# 531_RS26.net
KiCad netlist of a schematic drawn in Altium Designer
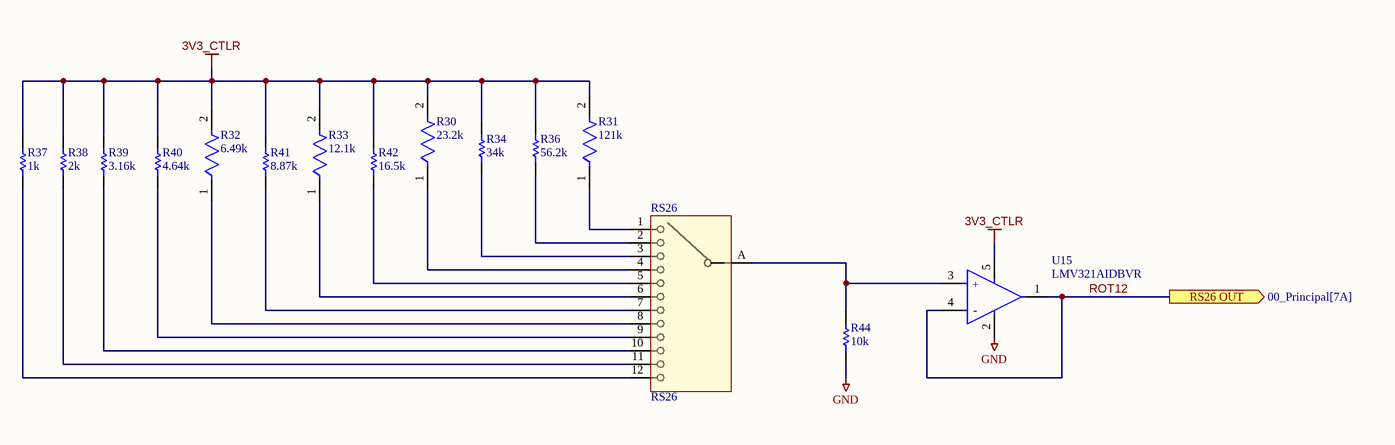
[diagram p0: 531_RS26.SchDoc]

(export (version "E")
  (design (tool "Eeschema 10.0.6"))
  (components
    (comp (ref "R30")
      (value "23.2k")
      (footprint "FP-ERJ2R-MFG")
      (description "RES SMD 23.2K OHM 1% 1/10W 0402")
      (fields
        (field (name "MANUFACTURER PART NUMBER") "ERJ-2RKF2322X")
        (field (name "MANUFACTURER") "Panasonic")
      )
      (libsource (lib "Altium Content Vault") (part "1029c3af85768c4190bb7ad29bc67b5"))
    )
    (comp (ref "R31")
      (value "121k")
      (footprint "FP-ERJ2R-MFG")
      (description "RES SMD 121K OHM 1% 1/10W 0402")
      (fields
        (field (name "OCTOPART") "https://octopart.com/erj-2rkf1213x-panasonic-55420883")
        (field (name "MANUFACTURER") "Panasonic")
      )
      (libsource (lib "Altium Content Vault") (part "1029c3af85768c4190bb7ad29bc67b5"))
    )
    (comp (ref "R32")
      (value "6.49k")
      (footprint "FP-ERJ2RK-MFG")
      (fields (field (name "TOLERANCE") "1%"))
      (libsource (lib "Altium Content Vault") (part "1029c3af85768c4190bb7ad29bc67b5"))
    )
    (comp (ref "R33")
      (value "12.1k")
      (footprint "FP-ERJ2RK-IPC_C")
      (description "RES SMD 12.1K OHM 1% 1/10W 0402")
      (fields (field (name "TOLERANCE") "1%"))
      (libsource (lib "Altium Content Vault") (part "1029c3af85768c4190bb7ad29bc67b5"))
    )
    (comp (ref "R34")
      (value "34k")
      (footprint "RESC1005X40X25LL05T05")
      (fields (field (name "PART NUMBER") "ERJ-2RKF3402X") (field (name "MANUFACTURER") "Panasonic"))
      (libsource (lib "Altium Content Vault") (part "RES"))
    )
    (comp (ref "R36")
      (value "56.2k")
      (footprint "RESC1005X40X25LL05T05")
      (fields (field (name "PART NUMBER") "ERJ-2RKF5622X") (field (name "MANUFACTURER") "Panasonic"))
      (libsource (lib "Altium Content Vault") (part "RES"))
    )
    (comp (ref "R37")
      (value "1k")
      (footprint "RESC1005X40X25NL05T05")
      (description "Chip Resistor, 1 KOhm, +/- 1%, 100 mW, -55 to 155 degC, 0402 (1005 Metric), RoHS, Tape and Reel")
      (fields (field (name "PARTNUMBER") "ERJ-2RKF1001X") (field (name "MANUFACTURER") "Basic Passives"))
      (libsource (lib "Altium Content Vault") (part "RES-2"))
    )
    (comp (ref "R38")
      (value "2k")
      (footprint "RESC1005X40X25LL10T10")
      (fields (field (name "MANUFACTURER") "Panasonic") (field (name "PART NUMBER") "ERA-2AEB202X"))
      (libsource (lib "Altium Content Vault") (part "RES"))
    )
    (comp (ref "R39")
      (value "3.16k")
      (footprint "RESC1005X40X25ML05T05")
      (fields (field (name "MANUFACTURER") "Panasonic") (field (name "PART NUMBER") "ERJ-2RKF3161X"))
      (libsource (lib "Altium Content Vault") (part "RES"))
    )
    (comp (ref "R40")
      (value "4.64k")
      (footprint "RESC1005X40X25LL05T05")
      (fields (field (name "PART NUMBER") "ERJ-2RKF4641X") (field (name "MANUFACTURER") "Panasonic"))
      (libsource (lib "Altium Content Vault") (part "RES"))
    )
    (comp (ref "R41")
      (value "8.87k")
      (footprint "RESC1005X40X25NL05T05")
      (fields (field (name "PART NUMBER") "ERJ-2RKF8871X") (field (name "MANUFACTURER") "Panasonic"))
      (libsource (lib "Altium Content Vault") (part "RES"))
    )
    (comp (ref "R42")
      (value "16.5k")
      (footprint "RESC1005X40X25LL05T05")
      (fields (field (name "PART NUMBER") "ERJ-2RKF1652X") (field (name "MANUFACTURER") "Panasonic"))
      (libsource (lib "Altium Content Vault") (part "RES"))
    )
    (comp (ref "R44")
      (value "10k")
      (footprint "RESC1005X40X25ML05T05")
      (fields (field (name "MANUFACTURER") "Panasonic") (field (name "PART NUMBER") "ERJ-2RHD1002X"))
      (libsource (lib "Altium Content Vault") (part "RES"))
    )
    (comp (ref "RS26")
      (value "RS26")
      (footprint "RS26")
      (description "RS26 Rotary Type Band Switch Position Switch")
      (libsource (lib "Esquemas") (part "RS26 Rotary Coder"))
    )
    (comp (ref "U15")
      (value "LMV321AIDBVR")
      (footprint "FP-DBV0005A-MFG")
      (description "IC OPAMP GP 1 CIRCUIT SOT23-5")
      (libsource (lib "Altium Content Vault") (part "1dcd28e651784f0a5a8ed6f8452eeff"))
    )
  )
  (nets
    (net (code "1") (name "/ROT12") (class "Default")
      (node (ref "U15") (pin "1") (pinfunction "OUT_1") (pintype "passive"))
      (node (ref "U15") (pin "4") (pinfunction "-IN_4") (pintype "tri_state"))
    )
    (net (code "2") (name "3V3_CTLR") (class "Default")
      (node (ref "R30") (pin "2") (pinfunction "2_2") (pintype "passive"))
      (node (ref "R31") (pin "2") (pinfunction "2_2") (pintype "passive"))
      (node (ref "R32") (pin "2") (pinfunction "2_2") (pintype "passive"))
      (node (ref "R33") (pin "2") (pinfunction "2_2") (pintype "passive"))
      (node (ref "R34") (pin "2") (pinfunction "2_2") (pintype "passive"))
      (node (ref "R36") (pin "2") (pinfunction "2_2") (pintype "passive"))
      (node (ref "R37") (pin "2") (pinfunction "2_2") (pintype "passive"))
      (node (ref "R38") (pin "2") (pinfunction "2_2") (pintype "passive"))
      (node (ref "R39") (pin "2") (pinfunction "2_2") (pintype "passive"))
      (node (ref "R40") (pin "2") (pinfunction "2_2") (pintype "passive"))
      (node (ref "R41") (pin "2") (pinfunction "2_2") (pintype "passive"))
      (node (ref "R42") (pin "2") (pinfunction "2_2") (pintype "passive"))
      (node (ref "U15") (pin "5") (pinfunction "V+_5") (pintype "passive"))
    )
    (net (code "3") (name "GND") (class "Default")
      (node (ref "R44") (pin "1") (pinfunction "1_1") (pintype "passive"))
      (node (ref "U15") (pin "2") (pinfunction "V-_2") (pintype "passive"))
    )
    (net (code "4") (name "Net-(R30-Pad1)") (class "Default")
      (node (ref "R30") (pin "1") (pinfunction "1_1") (pintype "passive"))
      (node (ref "RS26") (pin "4") (pinfunction "A_4") (pintype "passive"))
    )
    (net (code "5") (name "Net-(R31-Pad1)") (class "Default")
      (node (ref "R31") (pin "1") (pinfunction "1_1") (pintype "passive"))
      (node (ref "RS26") (pin "1") (pinfunction "A_1") (pintype "passive"))
    )
    (net (code "6") (name "Net-(R32-Pad1)") (class "Default")
      (node (ref "R32") (pin "1") (pinfunction "1_1") (pintype "passive"))
      (node (ref "RS26") (pin "8") (pinfunction "A_8") (pintype "passive"))
    )
    (net (code "7") (name "Net-(R33-Pad1)") (class "Default")
      (node (ref "R33") (pin "1") (pinfunction "1_1") (pintype "passive"))
      (node (ref "RS26") (pin "6") (pinfunction "A_6") (pintype "passive"))
    )
    (net (code "8") (name "Net-(R34-Pad1)") (class "Default")
      (node (ref "R34") (pin "1") (pinfunction "1_1") (pintype "passive"))
      (node (ref "RS26") (pin "3") (pinfunction "A_3") (pintype "passive"))
    )
    (net (code "9") (name "Net-(R36-Pad1)") (class "Default")
      (node (ref "R36") (pin "1") (pinfunction "1_1") (pintype "passive"))
      (node (ref "RS26") (pin "2") (pinfunction "A_2") (pintype "passive"))
    )
    (net (code "10") (name "Net-(R37-Pad1)") (class "Default")
      (node (ref "R37") (pin "1") (pinfunction "1_1") (pintype "passive"))
      (node (ref "RS26") (pin "12") (pinfunction "A_12") (pintype "passive"))
    )
    (net (code "11") (name "Net-(R38-Pad1)") (class "Default")
      (node (ref "R38") (pin "1") (pinfunction "1_1") (pintype "passive"))
      (node (ref "RS26") (pin "11") (pinfunction "A_11") (pintype "passive"))
    )
    (net (code "12") (name "Net-(R39-Pad1)") (class "Default")
      (node (ref "R39") (pin "1") (pinfunction "1_1") (pintype "passive"))
      (node (ref "RS26") (pin "10") (pinfunction "A_10") (pintype "passive"))
    )
    (net (code "13") (name "Net-(R40-Pad1)") (class "Default")
      (node (ref "R40") (pin "1") (pinfunction "1_1") (pintype "passive"))
      (node (ref "RS26") (pin "9") (pinfunction "A_9") (pintype "passive"))
    )
    (net (code "14") (name "Net-(R41-Pad1)") (class "Default")
      (node (ref "R41") (pin "1") (pinfunction "1_1") (pintype "passive"))
      (node (ref "RS26") (pin "7") (pinfunction "A_7") (pintype "passive"))
    )
    (net (code "15") (name "Net-(R42-Pad1)") (class "Default")
      (node (ref "R42") (pin "1") (pinfunction "1_1") (pintype "passive"))
      (node (ref "RS26") (pin "5") (pinfunction "A_5") (pintype "passive"))
    )
    (net (code "16") (name "Net-(U15-+IN)") (class "Default")
      (node (ref "R44") (pin "2") (pinfunction "2_2") (pintype "passive"))
      (node (ref "RS26") (pin "A") (pintype "passive"))
      (node (ref "U15") (pin "3") (pinfunction "+IN_3") (pintype "tri_state"))
    )
  )
)
